# stm32.net
KiCad netlist of a schematic drawn in Altium Designer
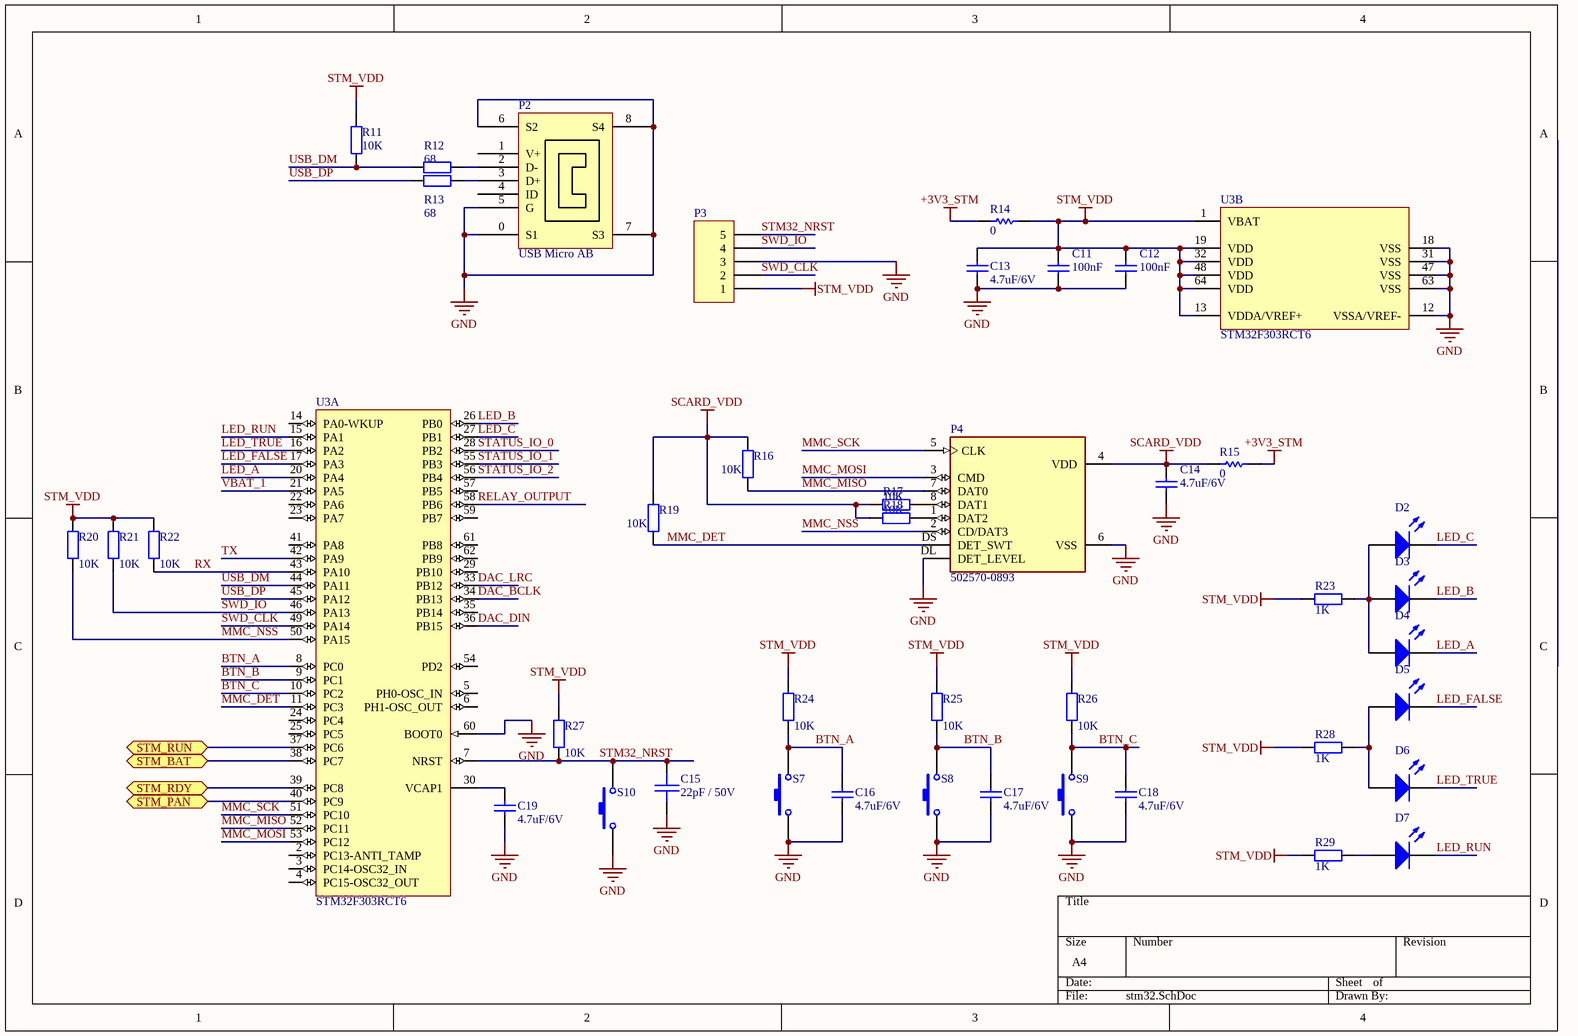
[diagram p0: stm32.SchDoc]

(export (version "E")
  (design (tool "Eeschema 10.0.6"))
  (components
    (comp (ref "C11")
      (value "100nF")
      (footprint "CR2012-0805")
      (description "Capacitor")
      (fields (field (name "PUBLISHER") "Altium Limited"))
      (libsource (lib "Miscellaneous Devices") (part "Cap"))
    )
    (comp (ref "C12")
      (value "100nF")
      (footprint "CR2012-0805")
      (description "Capacitor")
      (fields (field (name "PUBLISHER") "Altium Limited"))
      (libsource (lib "Miscellaneous Devices") (part "Cap"))
    )
    (comp (ref "C13")
      (value "4.7uF/6V")
      (footprint "CR2012-0805")
      (description "Capacitor (Semiconductor SIM Model)")
      (fields (field (name "PUBLISHER") "Altium Limited"))
      (libsource (lib "passive") (part "Cap Semi"))
    )
    (comp (ref "C14")
      (value "4.7uF/6V")
      (footprint "CR2012-0805")
      (description "Capacitor")
      (fields (field (name "PUBLISHER") "Altium Limited"))
      (libsource (lib "Miscellaneous Devices") (part "Cap"))
    )
    (comp (ref "C15")
      (value "22pF / 50V")
      (footprint "CR2012-0805")
      (description "Surface mount capacitor 0402")
      (libsource (lib "Vowstar_Basic_Device") (part "SMT_C_0402"))
    )
    (comp (ref "C16")
      (value "4.7uF/6V")
      (footprint "CR2012-0805")
      (description "Capacitor (Semiconductor SIM Model)")
      (fields (field (name "PUBLISHER") "Altium Limited"))
      (libsource (lib "passive") (part "Cap Semi"))
    )
    (comp (ref "C17")
      (value "4.7uF/6V")
      (footprint "CR2012-0805")
      (description "Capacitor (Semiconductor SIM Model)")
      (fields (field (name "PUBLISHER") "Altium Limited"))
      (libsource (lib "passive") (part "Cap Semi"))
    )
    (comp (ref "C18")
      (value "4.7uF/6V")
      (footprint "CR2012-0805")
      (description "Capacitor (Semiconductor SIM Model)")
      (fields (field (name "PUBLISHER") "Altium Limited"))
      (libsource (lib "passive") (part "Cap Semi"))
    )
    (comp (ref "C19")
      (value "4.7uF/6V")
      (footprint "CR2012-0805")
      (description "Capacitor (Semiconductor SIM Model)")
      (fields (field (name "PUBLISHER") "Altium Limited"))
      (libsource (lib "passive") (part "Cap Semi"))
    )
    (comp (ref "D2")
      (value "LED0")
      (footprint "LED1206")
      (description "Typical INFRARED GaAs LED")
      (fields (field (name "PUBLISHER") "Altium Limited"))
      (libsource (lib "Miscellaneous Devices") (part "LED0"))
    )
    (comp (ref "D3")
      (value "LED0")
      (footprint "LED1206")
      (description "Typical INFRARED GaAs LED")
      (fields (field (name "PUBLISHER") "Altium Limited"))
      (libsource (lib "Miscellaneous Devices") (part "LED0"))
    )
    (comp (ref "D4")
      (value "LED0")
      (footprint "LED1206")
      (description "Typical INFRARED GaAs LED")
      (fields (field (name "PUBLISHER") "Altium Limited"))
      (libsource (lib "Miscellaneous Devices") (part "LED0"))
    )
    (comp (ref "D5")
      (value "LED0")
      (footprint "LED1206")
      (description "Typical INFRARED GaAs LED")
      (fields (field (name "PUBLISHER") "Altium Limited"))
      (libsource (lib "Miscellaneous Devices") (part "LED0"))
    )
    (comp (ref "D6")
      (value "LED0")
      (footprint "LED1206")
      (description "Typical INFRARED GaAs LED")
      (fields (field (name "PUBLISHER") "Altium Limited"))
      (libsource (lib "Miscellaneous Devices") (part "LED0"))
    )
    (comp (ref "D7")
      (value "LED0")
      (footprint "LED1206")
      (description "Typical INFRARED GaAs LED")
      (fields (field (name "PUBLISHER") "Altium Limited"))
      (libsource (lib "Miscellaneous Devices") (part "LED0"))
    )
    (comp (ref "P2")
      (value "USB Micro AB")
      (footprint "USB_MICRO_wi_LEG")
      (description "USB Micro AB connector")
      (libsource (lib "passive") (part "USB Micro AB"))
    )
    (comp (ref "P3")
      (value "P?")
      (footprint "HDR1X5")
      (description "Header, 5-Pin")
      (fields (field (name "PUBLISHER") "Altium Limited"))
      (libsource (lib "Miscellaneous Connectors") (part "Header 5"))
    )
    (comp (ref "P4")
      (value "502570-0893")
      (footprint "MOLEX_502570-0893")
      (description "10 _8 + 2_ Position Card Connector Secure Digital - microSDâ„¢ Surface Mount, Right Angle Gold")
      (fields (field (name "MF") "Molex"))
      (libsource (lib "MMC-502570-0893") (part "502570-0893"))
    )
    (comp (ref "R11")
      (value "10K")
      (footprint "CR2012-0805")
      (description "Resistor")
      (fields (field (name "PUBLISHER") "Altium Limited"))
      (libsource (lib "") (part "Res2_3"))
    )
    (comp (ref "R12")
      (value "68")
      (footprint "CR2012-0805")
      (description "Resistor")
      (fields (field (name "PUBLISHER") "Altium Limited"))
      (libsource (lib "") (part "Res2_1"))
    )
    (comp (ref "R13")
      (value "68")
      (footprint "CR2012-0805")
      (description "Resistor")
      (fields (field (name "PUBLISHER") "Altium Limited"))
      (libsource (lib "") (part "Res2_1"))
    )
    (comp (ref "R14")
      (value "0")
      (footprint "JP1_SMD")
      (description "Semiconductor Resistor")
      (fields (field (name "PUBLISHER") "Altium Limited"))
      (libsource (lib "passive") (part "Res Semi"))
    )
    (comp (ref "R15")
      (value "0")
      (footprint "JP1_SMD")
      (description "Semiconductor Resistor")
      (fields (field (name "PUBLISHER") "Altium Limited"))
      (libsource (lib "passive") (part "Res Semi"))
    )
    (comp (ref "R16")
      (value "10K")
      (footprint "CR2012-0805")
      (description "Resistor")
      (fields (field (name "PUBLISHER") "Altium Limited"))
      (libsource (lib "") (part "Res2_3"))
    )
    (comp (ref "R17")
      (value "10K")
      (footprint "CR2012-0805")
      (description "Resistor")
      (fields (field (name "PUBLISHER") "Altium Limited"))
      (libsource (lib "") (part "Res2_1"))
    )
    (comp (ref "R18")
      (value "10K")
      (footprint "CR2012-0805")
      (description "Resistor")
      (fields (field (name "PUBLISHER") "Altium Limited"))
      (libsource (lib "") (part "Res2_1"))
    )
    (comp (ref "R19")
      (value "10K")
      (footprint "CR2012-0805")
      (description "Resistor")
      (fields (field (name "PUBLISHER") "Altium Limited"))
      (libsource (lib "") (part "Res2_3"))
    )
    (comp (ref "R20")
      (value "10K")
      (footprint "CR2012-0805")
      (description "Resistor")
      (fields (field (name "PUBLISHER") "Altium Limited"))
      (libsource (lib "") (part "Res2_2"))
    )
    (comp (ref "R21")
      (value "10K")
      (footprint "CR2012-0805")
      (description "Resistor")
      (fields (field (name "PUBLISHER") "Altium Limited"))
      (libsource (lib "") (part "Res2_2"))
    )
    (comp (ref "R22")
      (value "10K")
      (footprint "CR2012-0805")
      (description "Resistor")
      (fields (field (name "PUBLISHER") "Altium Limited"))
      (libsource (lib "") (part "Res2_2"))
    )
    (comp (ref "R23")
      (value "1K")
      (footprint "CR2012-0805")
      (description "Resistor")
      (fields (field (name "PUBLISHER") "Altium Limited"))
      (libsource (lib "Miscellaneous Devices") (part "Res2"))
    )
    (comp (ref "R24")
      (value "10K")
      (footprint "CR2012-0805")
      (description "Resistor")
      (fields (field (name "PUBLISHER") "Altium Limited"))
      (libsource (lib "") (part "Res2_2"))
    )
    (comp (ref "R25")
      (value "10K")
      (footprint "CR2012-0805")
      (description "Resistor")
      (fields (field (name "PUBLISHER") "Altium Limited"))
      (libsource (lib "") (part "Res2_2"))
    )
    (comp (ref "R26")
      (value "10K")
      (footprint "CR2012-0805")
      (description "Resistor")
      (fields (field (name "PUBLISHER") "Altium Limited"))
      (libsource (lib "") (part "Res2_2"))
    )
    (comp (ref "R27")
      (value "10K")
      (footprint "CR2012-0805")
      (description "Resistor")
      (fields (field (name "PUBLISHER") "Altium Limited"))
      (libsource (lib "") (part "Res2_3"))
    )
    (comp (ref "R28")
      (value "1K")
      (footprint "CR2012-0805")
      (description "Resistor")
      (fields (field (name "PUBLISHER") "Altium Limited"))
      (libsource (lib "Miscellaneous Devices") (part "Res2"))
    )
    (comp (ref "R29")
      (value "1K")
      (footprint "CR2012-0805")
      (description "Resistor")
      (fields (field (name "PUBLISHER") "Altium Limited"))
      (libsource (lib "Miscellaneous Devices") (part "Res2"))
    )
    (comp (ref "S7")
      (value "SW-PB")
      (footprint "pushbutton")
      (description "Switch")
      (fields (field (name "PUBLISHER") "Altium Limited"))
      (libsource (lib "Miscellaneous Devices") (part "SW-PB"))
    )
    (comp (ref "S8")
      (value "SW-PB")
      (footprint "pushbutton")
      (description "Switch")
      (fields (field (name "PUBLISHER") "Altium Limited"))
      (libsource (lib "Miscellaneous Devices") (part "SW-PB"))
    )
    (comp (ref "S9")
      (value "SW-PB")
      (footprint "pushbutton")
      (description "Switch")
      (fields (field (name "PUBLISHER") "Altium Limited"))
      (libsource (lib "Miscellaneous Devices") (part "SW-PB"))
    )
    (comp (ref "S10")
      (value "SW-PB")
      (footprint "pushbutton")
      (description "Switch")
      (fields (field (name "PUBLISHER") "Altium Limited"))
      (libsource (lib "Miscellaneous Devices") (part "SW-PB"))
    )
    (comp (ref "U3")
      (value "STM32F303RCT6")
      (footprint "STM-LQFP64_N")
      (fields (field (name "MANUFACTURER") "STMicroelectronics") (field (name "PARTNUMBER") "STM32F401RCT6"))
      (libsource (lib "STMicroelectronics STM32 F4") (part "STM32F401RCT6"))
    )
  )
  (nets
    (net (code "1") (name "+3V3_STM") (class "Default")
      (node (ref "R14") (pin "1") (pinfunction "1_1") (pintype "passive"))
      (node (ref "R15") (pin "1") (pinfunction "1_1") (pintype "passive"))
    )
    (net (code "2") (name "/BTN_A") (class "Default")
      (node (ref "C16") (pin "2") (pinfunction "2_2") (pintype "passive"))
      (node (ref "R24") (pin "2") (pinfunction "2_2") (pintype "passive"))
      (node (ref "S7") (pin "2") (pinfunction "2_2") (pintype "passive"))
      (node (ref "U3") (pin "8") (pinfunction "PC0_8") (pintype "bidirectional"))
    )
    (net (code "3") (name "/BTN_B") (class "Default")
      (node (ref "C17") (pin "2") (pinfunction "2_2") (pintype "passive"))
      (node (ref "R25") (pin "2") (pinfunction "2_2") (pintype "passive"))
      (node (ref "S8") (pin "2") (pinfunction "2_2") (pintype "passive"))
      (node (ref "U3") (pin "9") (pinfunction "PC1_9") (pintype "bidirectional"))
    )
    (net (code "4") (name "/BTN_C") (class "Default")
      (node (ref "C18") (pin "2") (pinfunction "2_2") (pintype "passive"))
      (node (ref "R26") (pin "2") (pinfunction "2_2") (pintype "passive"))
      (node (ref "S9") (pin "2") (pinfunction "2_2") (pintype "passive"))
      (node (ref "U3") (pin "10") (pinfunction "PC2_10") (pintype "bidirectional"))
    )
    (net (code "5") (name "/DAC_BCLK") (class "Default")
      (node (ref "U3") (pin "34") (pinfunction "PB13_34") (pintype "bidirectional"))
    )
    (net (code "6") (name "/DAC_DIN") (class "Default")
      (node (ref "U3") (pin "36") (pinfunction "PB15_36") (pintype "bidirectional"))
    )
    (net (code "7") (name "/DAC_LRC") (class "Default")
      (node (ref "U3") (pin "33") (pinfunction "PB12_33") (pintype "bidirectional"))
    )
    (net (code "8") (name "/LED_A") (class "Default")
      (node (ref "D4") (pin "2") (pinfunction "K_2") (pintype "passive"))
      (node (ref "U3") (pin "20") (pinfunction "PA4_20") (pintype "bidirectional"))
    )
    (net (code "9") (name "/LED_B") (class "Default")
      (node (ref "D3") (pin "2") (pinfunction "K_2") (pintype "passive"))
      (node (ref "U3") (pin "26") (pinfunction "PB0_26") (pintype "bidirectional"))
    )
    (net (code "10") (name "/LED_C") (class "Default")
      (node (ref "D2") (pin "2") (pinfunction "K_2") (pintype "passive"))
      (node (ref "U3") (pin "27") (pinfunction "PB1_27") (pintype "bidirectional"))
    )
    (net (code "11") (name "/LED_FALSE") (class "Default")
      (node (ref "D5") (pin "2") (pinfunction "K_2") (pintype "passive"))
      (node (ref "U3") (pin "17") (pinfunction "PA3_17") (pintype "bidirectional"))
    )
    (net (code "12") (name "/LED_RUN") (class "Default")
      (node (ref "D7") (pin "2") (pinfunction "K_2") (pintype "passive"))
      (node (ref "U3") (pin "15") (pinfunction "PA1_15") (pintype "bidirectional"))
    )
    (net (code "13") (name "/LED_TRUE") (class "Default")
      (node (ref "D6") (pin "2") (pinfunction "K_2") (pintype "passive"))
      (node (ref "U3") (pin "16") (pinfunction "PA2_16") (pintype "bidirectional"))
    )
    (net (code "14") (name "/MMC_DET") (class "Default")
      (node (ref "P4") (pin "DS") (pinfunction "DET_SWT_DS") (pintype "passive"))
      (node (ref "R19") (pin "1") (pinfunction "1_1") (pintype "passive"))
      (node (ref "U3") (pin "11") (pinfunction "PC3_11") (pintype "bidirectional"))
    )
    (net (code "15") (name "/MMC_MISO") (class "Default")
      (node (ref "P4") (pin "7") (pinfunction "DAT0_7") (pintype "bidirectional"))
      (node (ref "R16") (pin "1") (pinfunction "1_1") (pintype "passive"))
      (node (ref "U3") (pin "52") (pinfunction "PC11_52") (pintype "bidirectional"))
    )
    (net (code "16") (name "/MMC_MOSI") (class "Default")
      (node (ref "P4") (pin "3") (pinfunction "CMD_3") (pintype "bidirectional"))
      (node (ref "U3") (pin "53") (pinfunction "PC12_53") (pintype "bidirectional"))
    )
    (net (code "17") (name "/MMC_NSS") (class "Default")
      (node (ref "P4") (pin "2") (pinfunction "CD/DAT3_2") (pintype "bidirectional"))
      (node (ref "R20") (pin "2") (pinfunction "2_2") (pintype "passive"))
      (node (ref "U3") (pin "50") (pinfunction "PA15_50") (pintype "bidirectional"))
    )
    (net (code "18") (name "/MMC_SCK") (class "Default")
      (node (ref "P4") (pin "5") (pinfunction "CLK_5") (pintype "input"))
      (node (ref "U3") (pin "51") (pinfunction "PC10_51") (pintype "bidirectional"))
    )
    (net (code "19") (name "/RELAY_OUTPUT") (class "Default")
      (node (ref "U3") (pin "58") (pinfunction "PB6_58") (pintype "bidirectional"))
    )
    (net (code "20") (name "/RX") (class "Default")
      (node (ref "R22") (pin "2") (pinfunction "2_2") (pintype "passive"))
      (node (ref "U3") (pin "43") (pinfunction "PA10_43") (pintype "bidirectional"))
    )
    (net (code "21") (name "/STATUS_IO_0") (class "Default")
      (node (ref "U3") (pin "28") (pinfunction "PB2_28") (pintype "bidirectional"))
    )
    (net (code "22") (name "/STATUS_IO_1") (class "Default")
      (node (ref "U3") (pin "55") (pinfunction "PB3_55") (pintype "bidirectional"))
    )
    (net (code "23") (name "/STATUS_IO_2") (class "Default")
      (node (ref "U3") (pin "56") (pinfunction "PB4_56") (pintype "bidirectional"))
    )
    (net (code "24") (name "/STM32_NRST") (class "Default")
      (node (ref "C15") (pin "1") (pinfunction "1_1") (pintype "passive"))
      (node (ref "P3") (pin "5") (pinfunction "5_5") (pintype "passive"))
      (node (ref "R27") (pin "1") (pinfunction "1_1") (pintype "passive"))
      (node (ref "S10") (pin "2") (pinfunction "2_2") (pintype "passive"))
      (node (ref "U3") (pin "7") (pinfunction "NRST_7") (pintype "bidirectional"))
    )
    (net (code "25") (name "/STM_BAT") (class "Default")
      (node (ref "U3") (pin "38") (pinfunction "PC7_38") (pintype "bidirectional"))
    )
    (net (code "26") (name "/STM_PAN") (class "Default")
      (node (ref "U3") (pin "40") (pinfunction "PC9_40") (pintype "bidirectional"))
    )
    (net (code "27") (name "/STM_RDY") (class "Default")
      (node (ref "U3") (pin "39") (pinfunction "PC8_39") (pintype "bidirectional"))
    )
    (net (code "28") (name "/STM_RUN") (class "Default")
      (node (ref "U3") (pin "37") (pinfunction "PC6_37") (pintype "bidirectional"))
    )
    (net (code "29") (name "/SWD_CLK") (class "Default")
      (node (ref "P3") (pin "2") (pinfunction "2_2") (pintype "passive"))
      (node (ref "U3") (pin "49") (pinfunction "PA14_49") (pintype "bidirectional"))
    )
    (net (code "30") (name "/SWD_IO") (class "Default")
      (node (ref "P3") (pin "4") (pinfunction "4_4") (pintype "passive"))
      (node (ref "R21") (pin "2") (pinfunction "2_2") (pintype "passive"))
      (node (ref "U3") (pin "46") (pinfunction "PA13_46") (pintype "bidirectional"))
    )
    (net (code "31") (name "/TX") (class "Default")
      (node (ref "U3") (pin "42") (pinfunction "PA9_42") (pintype "bidirectional"))
    )
    (net (code "32") (name "/USB_DM") (class "Default")
      (node (ref "R11") (pin "1") (pinfunction "1_1") (pintype "passive"))
      (node (ref "R12") (pin "1") (pinfunction "1_1") (pintype "passive"))
      (node (ref "U3") (pin "44") (pinfunction "PA11_44") (pintype "bidirectional"))
    )
    (net (code "33") (name "/USB_DP") (class "Default")
      (node (ref "R13") (pin "1") (pinfunction "1_1") (pintype "passive"))
      (node (ref "U3") (pin "45") (pinfunction "PA12_45") (pintype "bidirectional"))
    )
    (net (code "34") (name "/VBAT_1") (class "Default")
      (node (ref "U3") (pin "21") (pinfunction "PA5_21") (pintype "bidirectional"))
    )
    (net (code "35") (name "GND") (class "Default")
      (node (ref "C11") (pin "1") (pinfunction "1_1") (pintype "passive"))
      (node (ref "C12") (pin "1") (pinfunction "1_1") (pintype "passive"))
      (node (ref "C13") (pin "1") (pinfunction "1_1") (pintype "passive"))
      (node (ref "C14") (pin "1") (pinfunction "1_1") (pintype "passive"))
      (node (ref "C15") (pin "2") (pinfunction "2_2") (pintype "passive"))
      (node (ref "C16") (pin "1") (pinfunction "1_1") (pintype "passive"))
      (node (ref "C17") (pin "1") (pinfunction "1_1") (pintype "passive"))
      (node (ref "C18") (pin "1") (pinfunction "1_1") (pintype "passive"))
      (node (ref "C19") (pin "1") (pinfunction "1_1") (pintype "passive"))
      (node (ref "P2") (pin "0") (pinfunction "S1_0") (pintype "passive"))
      (node (ref "P2") (pin "5") (pinfunction "G_5") (pintype "passive"))
      (node (ref "P2") (pin "6") (pinfunction "S2_6") (pintype "passive"))
      (node (ref "P2") (pin "7") (pinfunction "S3_7") (pintype "passive"))
      (node (ref "P2") (pin "8") (pinfunction "S4_8") (pintype "passive"))
      (node (ref "P3") (pin "3") (pinfunction "3_3") (pintype "passive"))
      (node (ref "P4") (pin "6") (pinfunction "VSS_6") (pintype "power_in"))
      (node (ref "P4") (pin "DL") (pinfunction "DET_LEVEL_DL") (pintype "passive"))
      (node (ref "S10") (pin "1") (pinfunction "1_1") (pintype "passive"))
      (node (ref "S7") (pin "1") (pinfunction "1_1") (pintype "passive"))
      (node (ref "S8") (pin "1") (pinfunction "1_1") (pintype "passive"))
      (node (ref "S9") (pin "1") (pinfunction "1_1") (pintype "passive"))
      (node (ref "U3") (pin "12") (pinfunction "VSSA/VREF-_12") (pintype "power_in"))
      (node (ref "U3") (pin "18") (pinfunction "VSS_18") (pintype "power_in"))
      (node (ref "U3") (pin "31") (pinfunction "VSS_31") (pintype "power_in"))
      (node (ref "U3") (pin "47") (pinfunction "VSS_47") (pintype "power_in"))
      (node (ref "U3") (pin "60") (pinfunction "BOOT0_60") (pintype "input"))
      (node (ref "U3") (pin "63") (pinfunction "VSS_63") (pintype "power_in"))
    )
    (net (code "36") (name "Net-(D2-A)") (class "Default")
      (node (ref "D2") (pin "1") (pinfunction "A_1") (pintype "passive"))
      (node (ref "D3") (pin "1") (pinfunction "A_1") (pintype "passive"))
      (node (ref "D4") (pin "1") (pinfunction "A_1") (pintype "passive"))
      (node (ref "R23") (pin "1") (pinfunction "1_1") (pintype "passive"))
    )
    (net (code "37") (name "Net-(D5-A)") (class "Default")
      (node (ref "D5") (pin "1") (pinfunction "A_1") (pintype "passive"))
      (node (ref "D6") (pin "1") (pinfunction "A_1") (pintype "passive"))
      (node (ref "R28") (pin "1") (pinfunction "1_1") (pintype "passive"))
    )
    (net (code "38") (name "Net-(D7-A)") (class "Default")
      (node (ref "D7") (pin "1") (pinfunction "A_1") (pintype "passive"))
      (node (ref "R29") (pin "1") (pinfunction "1_1") (pintype "passive"))
    )
    (net (code "39") (name "Net-(P2-D+)") (class "Default")
      (node (ref "P2") (pin "3") (pinfunction "D+_3") (pintype "passive"))
      (node (ref "R13") (pin "2") (pinfunction "2_2") (pintype "passive"))
    )
    (net (code "40") (name "Net-(P2-D-)") (class "Default")
      (node (ref "P2") (pin "2") (pinfunction "D-_2") (pintype "passive"))
      (node (ref "R12") (pin "2") (pinfunction "2_2") (pintype "passive"))
    )
    (net (code "41") (name "Net-(P4-DAT1)") (class "Default")
      (node (ref "P4") (pin "8") (pinfunction "DAT1_8") (pintype "bidirectional"))
      (node (ref "R17") (pin "2") (pinfunction "2_2") (pintype "passive"))
    )
    (net (code "42") (name "Net-(P4-DAT2)") (class "Default")
      (node (ref "P4") (pin "1") (pinfunction "DAT2_1") (pintype "bidirectional"))
      (node (ref "R18") (pin "2") (pinfunction "2_2") (pintype "passive"))
    )
    (net (code "43") (name "Net-(U3A-VCAP1)") (class "Default")
      (node (ref "C19") (pin "2") (pinfunction "2_2") (pintype "passive"))
      (node (ref "U3") (pin "30") (pinfunction "VCAP1_30") (pintype "power_in"))
    )
    (net (code "44") (name "SCARD_VDD") (class "Default")
      (node (ref "C14") (pin "2") (pinfunction "2_2") (pintype "passive"))
      (node (ref "P4") (pin "4") (pinfunction "VDD_4") (pintype "power_in"))
      (node (ref "R15") (pin "2") (pinfunction "2_2") (pintype "passive"))
      (node (ref "R16") (pin "2") (pinfunction "2_2") (pintype "passive"))
      (node (ref "R17") (pin "1") (pinfunction "1_1") (pintype "passive"))
      (node (ref "R18") (pin "1") (pinfunction "1_1") (pintype "passive"))
      (node (ref "R19") (pin "2") (pinfunction "2_2") (pintype "passive"))
    )
    (net (code "45") (name "STM_VDD") (class "Default")
      (node (ref "C11") (pin "2") (pinfunction "2_2") (pintype "passive"))
      (node (ref "C12") (pin "2") (pinfunction "2_2") (pintype "passive"))
      (node (ref "C13") (pin "2") (pinfunction "2_2") (pintype "passive"))
      (node (ref "P3") (pin "1") (pinfunction "1_1") (pintype "passive"))
      (node (ref "R11") (pin "2") (pinfunction "2_2") (pintype "passive"))
      (node (ref "R14") (pin "2") (pinfunction "2_2") (pintype "passive"))
      (node (ref "R20") (pin "1") (pinfunction "1_1") (pintype "passive"))
      (node (ref "R21") (pin "1") (pinfunction "1_1") (pintype "passive"))
      (node (ref "R22") (pin "1") (pinfunction "1_1") (pintype "passive"))
      (node (ref "R23") (pin "2") (pinfunction "2_2") (pintype "passive"))
      (node (ref "R24") (pin "1") (pinfunction "1_1") (pintype "passive"))
      (node (ref "R25") (pin "1") (pinfunction "1_1") (pintype "passive"))
      (node (ref "R26") (pin "1") (pinfunction "1_1") (pintype "passive"))
      (node (ref "R27") (pin "2") (pinfunction "2_2") (pintype "passive"))
      (node (ref "R28") (pin "2") (pinfunction "2_2") (pintype "passive"))
      (node (ref "R29") (pin "2") (pinfunction "2_2") (pintype "passive"))
      (node (ref "U3") (pin "1") (pinfunction "VBAT_1") (pintype "power_in"))
      (node (ref "U3") (pin "13") (pinfunction "VDDA/VREF+_13") (pintype "power_in"))
      (node (ref "U3") (pin "19") (pinfunction "VDD_19") (pintype "power_in"))
      (node (ref "U3") (pin "32") (pinfunction "VDD_32") (pintype "power_in"))
      (node (ref "U3") (pin "48") (pinfunction "VDD_48") (pintype "power_in"))
      (node (ref "U3") (pin "64") (pinfunction "VDD_64") (pintype "power_in"))
    )
    (net (code "46") (name "unconnected-(P2-ID-Pad4)") (class "Default")
      (node (ref "P2") (pin "4") (pinfunction "ID_4") (pintype "passive"))
    )
    (net (code "47") (name "unconnected-(P2-V+-Pad1)") (class "Default")
      (node (ref "P2") (pin "1") (pinfunction "V+_1") (pintype "passive"))
    )
    (net (code "48") (name "unconnected-(U3A-PA0-WKUP-Pad14)") (class "Default")
      (node (ref "U3") (pin "14") (pinfunction "PA0-WKUP_14") (pintype "bidirectional"))
    )
    (net (code "49") (name "unconnected-(U3A-PA6-Pad22)") (class "Default")
      (node (ref "U3") (pin "22") (pinfunction "PA6_22") (pintype "bidirectional"))
    )
    (net (code "50") (name "unconnected-(U3A-PA7-Pad23)") (class "Default")
      (node (ref "U3") (pin "23") (pinfunction "PA7_23") (pintype "bidirectional"))
    )
    (net (code "51") (name "unconnected-(U3A-PA8-Pad41)") (class "Default")
      (node (ref "U3") (pin "41") (pinfunction "PA8_41") (pintype "bidirectional"))
    )
    (net (code "52") (name "unconnected-(U3A-PB5-Pad57)") (class "Default")
      (node (ref "U3") (pin "57") (pinfunction "PB5_57") (pintype "bidirectional"))
    )
    (net (code "53") (name "unconnected-(U3A-PB7-Pad59)") (class "Default")
      (node (ref "U3") (pin "59") (pinfunction "PB7_59") (pintype "bidirectional"))
    )
    (net (code "54") (name "unconnected-(U3A-PB8-Pad61)") (class "Default")
      (node (ref "U3") (pin "61") (pinfunction "PB8_61") (pintype "bidirectional"))
    )
    (net (code "55") (name "unconnected-(U3A-PB9-Pad62)") (class "Default")
      (node (ref "U3") (pin "62") (pinfunction "PB9_62") (pintype "bidirectional"))
    )
    (net (code "56") (name "unconnected-(U3A-PB10-Pad29)") (class "Default")
      (node (ref "U3") (pin "29") (pinfunction "PB10_29") (pintype "bidirectional"))
    )
    (net (code "57") (name "unconnected-(U3A-PB14-Pad35)") (class "Default")
      (node (ref "U3") (pin "35") (pinfunction "PB14_35") (pintype "bidirectional"))
    )
    (net (code "58") (name "unconnected-(U3A-PC4-Pad24)") (class "Default")
      (node (ref "U3") (pin "24") (pinfunction "PC4_24") (pintype "bidirectional"))
    )
    (net (code "59") (name "unconnected-(U3A-PC5-Pad25)") (class "Default")
      (node (ref "U3") (pin "25") (pinfunction "PC5_25") (pintype "bidirectional"))
    )
    (net (code "60") (name "unconnected-(U3A-PC13-ANTI_TAMP-Pad2)") (class "Default")
      (node (ref "U3") (pin "2") (pinfunction "PC13-ANTI_TAMP_2") (pintype "bidirectional"))
    )
    (net (code "61") (name "unconnected-(U3A-PC14-OSC32_IN-Pad3)") (class "Default")
      (node (ref "U3") (pin "3") (pinfunction "PC14-OSC32_IN_3") (pintype "bidirectional"))
    )
    (net (code "62") (name "unconnected-(U3A-PC15-OSC32_OUT-Pad4)") (class "Default")
      (node (ref "U3") (pin "4") (pinfunction "PC15-OSC32_OUT_4") (pintype "bidirectional"))
    )
    (net (code "63") (name "unconnected-(U3A-PD2-Pad54)") (class "Default")
      (node (ref "U3") (pin "54") (pinfunction "PD2_54") (pintype "bidirectional"))
    )
    (net (code "64") (name "unconnected-(U3A-PH0-OSC_IN-Pad5)") (class "Default")
      (node (ref "U3") (pin "5") (pinfunction "PH0-OSC_IN_5") (pintype "bidirectional"))
    )
    (net (code "65") (name "unconnected-(U3A-PH1-OSC_OUT-Pad6)") (class "Default")
      (node (ref "U3") (pin "6") (pinfunction "PH1-OSC_OUT_6") (pintype "bidirectional"))
    )
  )
)
